# Extension_sheet.net
KiCad netlist of a schematic drawn in Altium Designer
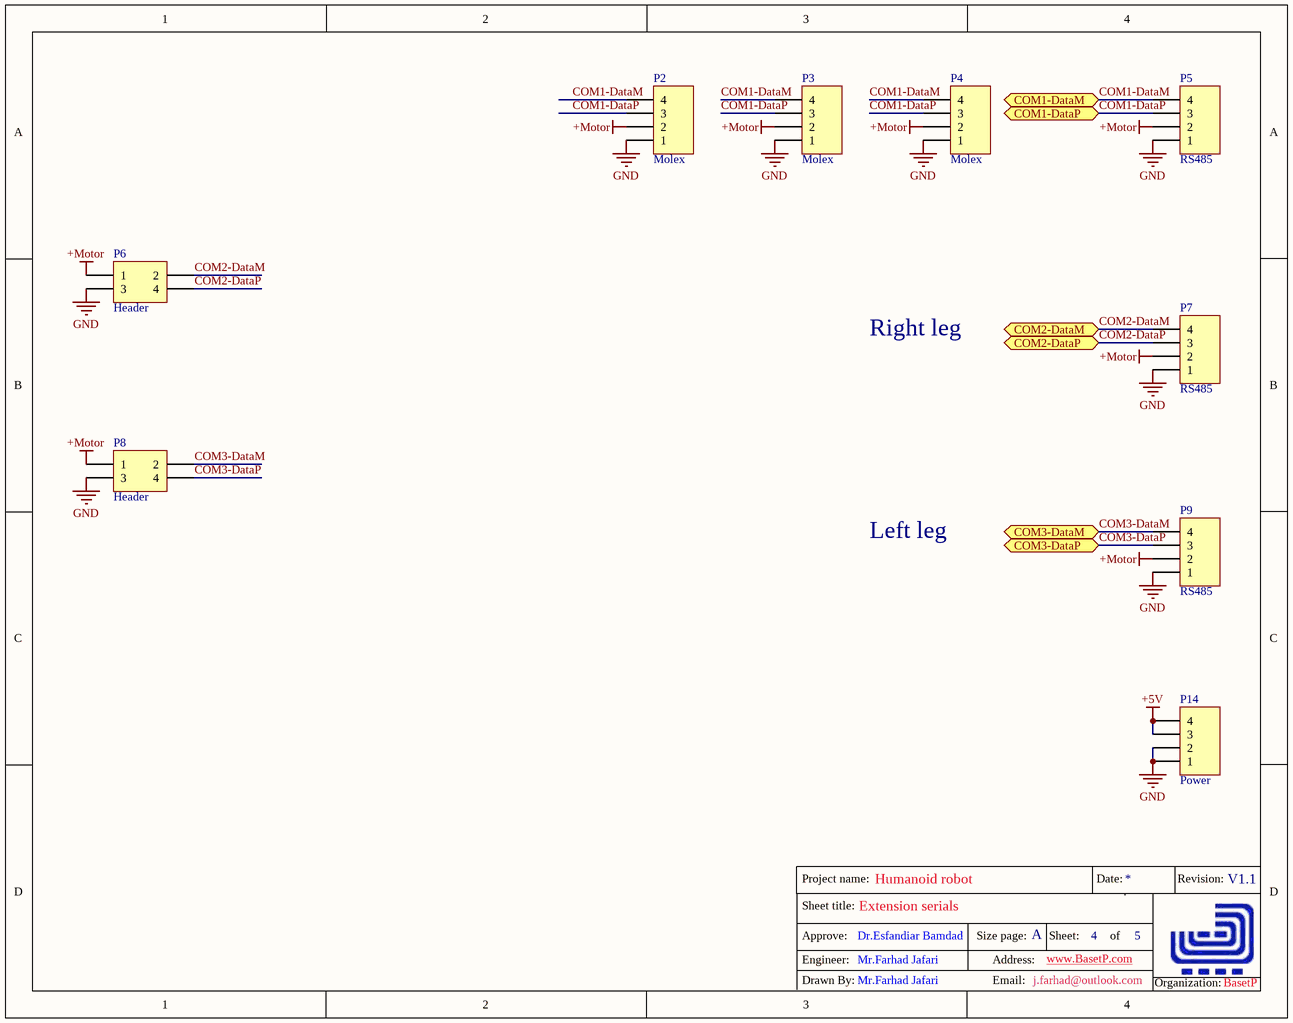
[diagram p0: Extension sheet.SchDoc]

(export (version "E")
  (design (tool "Eeschema 10.0.6"))
  (components
    (comp (ref "P2")
      (value "Molex")
      (footprint "HDR1*4")
      (description "Molex pin circular")
      (libsource (lib "Farhad_Library") (part "Molex 4pin"))
    )
    (comp (ref "P3")
      (value "Molex")
      (footprint "HDR1*4")
      (description "Molex pin circular")
      (libsource (lib "Farhad_Library") (part "Molex 4pin"))
    )
    (comp (ref "P4")
      (value "Molex")
      (footprint "HDR1*4")
      (description "Molex pin circular")
      (libsource (lib "Farhad_Library") (part "Molex 4pin"))
    )
    (comp (ref "P5")
      (value "RS485")
      (footprint "HDR1*4")
      (description "Molex pin circular")
      (libsource (lib "Farhad_Library") (part "Molex 4pin"))
    )
    (comp (ref "P6")
      (value "Header")
      (footprint "connector 2*2")
      (description "Header, 4-Pin, 2X2 right angle")
      (fields (field (name "PUBLISHER") "Altium Limited"))
      (libsource (lib "Farhad_Library") (part "Header 2X2 right angle"))
    )
    (comp (ref "P7")
      (value "RS485")
      (footprint "HDR1*4")
      (description "Molex pin circular")
      (libsource (lib "Farhad_Library") (part "Molex 4pin"))
    )
    (comp (ref "P8")
      (value "Header")
      (footprint "connector 2*2")
      (description "Header, 4-Pin, 2X2 right angle")
      (fields (field (name "PUBLISHER") "Altium Limited"))
      (libsource (lib "Farhad_Library") (part "Header 2X2 right angle"))
    )
    (comp (ref "P9")
      (value "RS485")
      (footprint "HDR1*4")
      (description "Molex pin circular")
      (libsource (lib "Farhad_Library") (part "Molex 4pin"))
    )
    (comp (ref "P14")
      (value "Power")
      (footprint "HDR1X4")
      (description "Header, 4-Pin")
      (fields (field (name "PUBLISHER") "Altium Limited"))
      (libsource (lib "Farhad_Library") (part "Header 4"))
    )
  )
  (nets
    (net (code "1") (name "+5V") (class "Default")
      (node (ref "P14") (pin "3") (pinfunction "3_3") (pintype "passive"))
      (node (ref "P14") (pin "4") (pinfunction "4_4") (pintype "passive"))
    )
    (net (code "2") (name "+Motor") (class "Default")
      (node (ref "P2") (pin "2") (pinfunction "2_2") (pintype "passive"))
      (node (ref "P3") (pin "2") (pinfunction "2_2") (pintype "passive"))
      (node (ref "P4") (pin "2") (pinfunction "2_2") (pintype "passive"))
      (node (ref "P5") (pin "2") (pinfunction "2_2") (pintype "passive"))
      (node (ref "P6") (pin "1") (pinfunction "1_1") (pintype "passive"))
      (node (ref "P7") (pin "2") (pinfunction "2_2") (pintype "passive"))
      (node (ref "P8") (pin "1") (pinfunction "1_1") (pintype "passive"))
      (node (ref "P9") (pin "2") (pinfunction "2_2") (pintype "passive"))
    )
    (net (code "3") (name "/COM1-DataM") (class "Default")
      (node (ref "P2") (pin "4") (pinfunction "4_4") (pintype "passive"))
      (node (ref "P3") (pin "4") (pinfunction "4_4") (pintype "passive"))
      (node (ref "P4") (pin "4") (pinfunction "4_4") (pintype "passive"))
      (node (ref "P5") (pin "4") (pinfunction "4_4") (pintype "passive"))
    )
    (net (code "4") (name "/COM1-DataP") (class "Default")
      (node (ref "P2") (pin "3") (pinfunction "3_3") (pintype "passive"))
      (node (ref "P3") (pin "3") (pinfunction "3_3") (pintype "passive"))
      (node (ref "P4") (pin "3") (pinfunction "3_3") (pintype "passive"))
      (node (ref "P5") (pin "3") (pinfunction "3_3") (pintype "passive"))
    )
    (net (code "5") (name "/COM2-DataM") (class "Default")
      (node (ref "P6") (pin "2") (pinfunction "2_2") (pintype "passive"))
      (node (ref "P7") (pin "4") (pinfunction "4_4") (pintype "passive"))
    )
    (net (code "6") (name "/COM2-DataP") (class "Default")
      (node (ref "P6") (pin "4") (pinfunction "4_4") (pintype "passive"))
      (node (ref "P7") (pin "3") (pinfunction "3_3") (pintype "passive"))
    )
    (net (code "7") (name "/COM3-DataM") (class "Default")
      (node (ref "P8") (pin "2") (pinfunction "2_2") (pintype "passive"))
      (node (ref "P9") (pin "4") (pinfunction "4_4") (pintype "passive"))
    )
    (net (code "8") (name "/COM3-DataP") (class "Default")
      (node (ref "P8") (pin "4") (pinfunction "4_4") (pintype "passive"))
      (node (ref "P9") (pin "3") (pinfunction "3_3") (pintype "passive"))
    )
    (net (code "9") (name "GND") (class "Default")
      (node (ref "P14") (pin "1") (pinfunction "1_1") (pintype "passive"))
      (node (ref "P14") (pin "2") (pinfunction "2_2") (pintype "passive"))
      (node (ref "P2") (pin "1") (pinfunction "1_1") (pintype "passive"))
      (node (ref "P3") (pin "1") (pinfunction "1_1") (pintype "passive"))
      (node (ref "P4") (pin "1") (pinfunction "1_1") (pintype "passive"))
      (node (ref "P5") (pin "1") (pinfunction "1_1") (pintype "passive"))
      (node (ref "P6") (pin "3") (pinfunction "3_3") (pintype "passive"))
      (node (ref "P7") (pin "1") (pinfunction "1_1") (pintype "passive"))
      (node (ref "P8") (pin "3") (pinfunction "3_3") (pintype "passive"))
      (node (ref "P9") (pin "1") (pinfunction "1_1") (pintype "passive"))
    )
  )
)
